# servoUSBrev0.net
KiCad netlist of a schematic drawn in Altium Designer
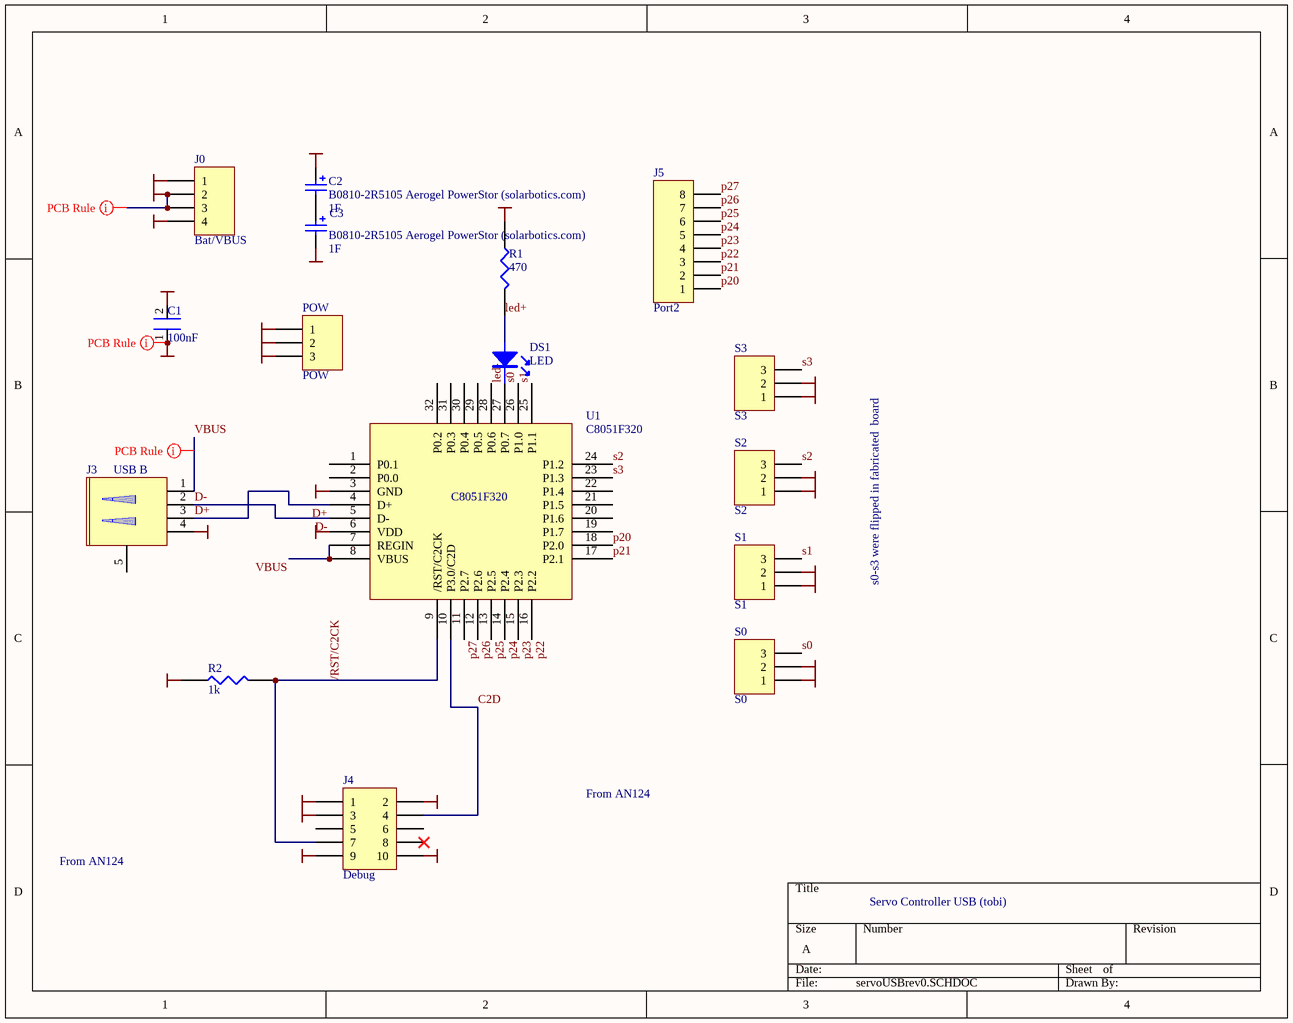
[diagram p0: servoUSBrev0.SCHDOC]

(export (version "E")
  (design (tool "Eeschema 10.0.6"))
  (components
    (comp (ref "C1")
      (value "100nF")
      (footprint "CC2013-0805")
      (libsource (lib "tobi SCHEMATIC") (part "CAPCHIP"))
    )
    (comp (ref "C2")
      (value "B0810-2R5105 Aerogel PowerStor (solarbotics.com)")
      (footprint "Capacitor - Electrolytic:CAPPR3.5-8X10.5")
      (description "Polarized Capacitor (Radial)")
      (fields (field (name "ALTIUM_VALUE") "1F") (field (name "PUBLISHER") "Altium Limited"))
      (libsource (lib "Miscellaneous Devices") (part "Cap Pol1"))
    )
    (comp (ref "C3")
      (value "B0810-2R5105 Aerogel PowerStor (solarbotics.com)")
      (footprint "Capacitor - Electrolytic:CAPPR3.5-8X10.5")
      (description "Polarized Capacitor (Radial)")
      (fields (field (name "ALTIUM_VALUE") "1F") (field (name "PUBLISHER") "Altium Limited"))
      (libsource (lib "Miscellaneous Devices") (part "Cap Pol1"))
    )
    (comp (ref "DS1")
      (value "LED")
      (footprint "0805LED")
      (description "LED, SMT 3mm by 1.5mm")
      (libsource (lib "SimpleMonitorUSBAER") (part "LED"))
    )
    (comp (ref "J0")
      (value "Bat/VBUS")
      (footprint "HDR1X4")
      (description "Header, 4-Pin")
      (fields (field (name "PUBLISHER") "Altium Limited"))
      (libsource (lib "Miscellaneous Connectors") (part "Header 4"))
    )
    (comp (ref "J3")
      (value "USB B")
      (footprint "usb")
      (description "USB TypB")
      (libsource (lib "DAC") (part "USB"))
    )
    (comp (ref "J4")
      (value "Debug")
      (footprint "HDR2X5")
      (description "Header, 5-Pin, Dual row")
      (fields (field (name "PUBLISHER") "Altium Limited"))
      (libsource (lib "Miscellaneous Connectors") (part "Header 5X2"))
    )
    (comp (ref "J5")
      (value "Port2")
      (footprint "HDR1X8")
      (description "Header, 8-Pin")
      (fields (field (name "PUBLISHER") "Altium Limited"))
      (libsource (lib "Miscellaneous Connectors") (part "Header 8"))
    )
    (comp (ref "POW")
      (value "POW")
      (footprint "HDR1X3")
      (description "Header, 3-Pin")
      (fields (field (name "PUBLISHER") "Altium Limited"))
      (libsource (lib "") (part "Header 3_1"))
    )
    (comp (ref "R1") (value "470") (footprint "CR2012-0805") (libsource (lib "*") (part "RES1")))
    (comp (ref "R2") (value "1k") (footprint "CR2012-0805") (libsource (lib "*") (part "RES1")))
    (comp (ref "S0")
      (value "S0")
      (footprint "HDR1X3")
      (description "Header, 3-Pin")
      (fields (field (name "PUBLISHER") "Altium Limited"))
      (libsource (lib "Miscellaneous Connectors") (part "Header 3"))
    )
    (comp (ref "S1")
      (value "S1")
      (footprint "HDR1X3")
      (description "Header, 3-Pin")
      (fields (field (name "PUBLISHER") "Altium Limited"))
      (libsource (lib "Miscellaneous Connectors") (part "Header 3"))
    )
    (comp (ref "S2")
      (value "S2")
      (footprint "HDR1X3")
      (description "Header, 3-Pin")
      (fields (field (name "PUBLISHER") "Altium Limited"))
      (libsource (lib "Miscellaneous Connectors") (part "Header 3"))
    )
    (comp (ref "S3")
      (value "S3")
      (footprint "HDR1X3")
      (description "Header, 3-Pin")
      (fields (field (name "PUBLISHER") "Altium Limited"))
      (libsource (lib "Miscellaneous Connectors") (part "Header 3"))
    )
    (comp (ref "U1")
      (value "C8051F320")
      (footprint "TQFP32")
      (description "Silicon Labs USB Microcontroller")
      (libsource (lib "tobi SCHEMATIC") (part "C8051F320"))
    )
  )
  (nets
    (net (code "1") (name "/C2D") (class "Default")
      (node (ref "J4") (pin "4") (pinfunction "4_4") (pintype "passive"))
      (node (ref "U1") (pin "10") (pinfunction "P3.0/C2D_10") (pintype "passive"))
    )
    (net (code "2") (name "/D+") (class "Default")
      (node (ref "J3") (pin "3") (pintype "passive"))
      (node (ref "U1") (pin "4") (pinfunction "D+_4") (pintype "passive"))
    )
    (net (code "3") (name "/D-") (class "Default")
      (node (ref "J3") (pin "2") (pintype "passive"))
      (node (ref "U1") (pin "5") (pinfunction "D-_5") (pintype "passive"))
    )
    (net (code "4") (name "/led+") (class "Default")
      (node (ref "DS1") (pin "+") (pinfunction "1_+") (pintype "passive"))
      (node (ref "R1") (pin "2") (pinfunction "2_2") (pintype "passive"))
    )
    (net (code "5") (name "/led-") (class "Default")
      (node (ref "DS1") (pin "-") (pinfunction "2_-") (pintype "passive"))
      (node (ref "U1") (pin "27") (pinfunction "P0.7_27") (pintype "passive"))
    )
    (net (code "6") (name "/p20") (class "Default")
      (node (ref "J5") (pin "1") (pinfunction "1_1") (pintype "passive"))
      (node (ref "U1") (pin "18") (pinfunction "P2.0_18") (pintype "passive"))
    )
    (net (code "7") (name "/p21") (class "Default")
      (node (ref "J5") (pin "2") (pinfunction "2_2") (pintype "passive"))
      (node (ref "U1") (pin "17") (pinfunction "P2.1_17") (pintype "passive"))
    )
    (net (code "8") (name "/p22") (class "Default")
      (node (ref "J5") (pin "3") (pinfunction "3_3") (pintype "passive"))
      (node (ref "U1") (pin "16") (pinfunction "P2.2_16") (pintype "passive"))
    )
    (net (code "9") (name "/p23") (class "Default")
      (node (ref "J5") (pin "4") (pinfunction "4_4") (pintype "passive"))
      (node (ref "U1") (pin "15") (pinfunction "P2.3_15") (pintype "passive"))
    )
    (net (code "10") (name "/p24") (class "Default")
      (node (ref "J5") (pin "5") (pinfunction "5_5") (pintype "passive"))
      (node (ref "U1") (pin "14") (pinfunction "P2.4_14") (pintype "passive"))
    )
    (net (code "11") (name "/p25") (class "Default")
      (node (ref "J5") (pin "6") (pinfunction "6_6") (pintype "passive"))
      (node (ref "U1") (pin "13") (pinfunction "P2.5_13") (pintype "passive"))
    )
    (net (code "12") (name "/p26") (class "Default")
      (node (ref "J5") (pin "7") (pinfunction "7_7") (pintype "passive"))
      (node (ref "U1") (pin "12") (pinfunction "P2.6_12") (pintype "passive"))
    )
    (net (code "13") (name "/p27") (class "Default")
      (node (ref "J5") (pin "8") (pinfunction "8_8") (pintype "passive"))
      (node (ref "U1") (pin "11") (pinfunction "P2.7_11") (pintype "passive"))
    )
    (net (code "14") (name "/s0") (class "Default")
      (node (ref "S0") (pin "3") (pinfunction "3_3") (pintype "passive"))
      (node (ref "U1") (pin "26") (pinfunction "P1.0_26") (pintype "passive"))
    )
    (net (code "15") (name "/s1") (class "Default")
      (node (ref "S1") (pin "3") (pinfunction "3_3") (pintype "passive"))
      (node (ref "U1") (pin "25") (pinfunction "P1.1_25") (pintype "passive"))
    )
    (net (code "16") (name "/s2") (class "Default")
      (node (ref "S2") (pin "3") (pinfunction "3_3") (pintype "passive"))
      (node (ref "U1") (pin "24") (pinfunction "P1.2_24") (pintype "passive"))
    )
    (net (code "17") (name "/s3") (class "Default")
      (node (ref "S3") (pin "3") (pinfunction "3_3") (pintype "passive"))
      (node (ref "U1") (pin "23") (pinfunction "P1.3_23") (pintype "passive"))
    )
    (net (code "18") (name "/{slash}RST{slash}C2CK") (class "Default")
      (node (ref "J4") (pin "7") (pinfunction "7_7") (pintype "passive"))
      (node (ref "R2") (pin "2") (pinfunction "2_2") (pintype "passive"))
      (node (ref "U1") (pin "9") (pinfunction "/RST/C2CK_9") (pintype "passive"))
    )
    (net (code "19") (name "GND") (class "Default")
      (node (ref "C1") (pin "1") (pintype "passive"))
      (node (ref "C3") (pin "2") (pinfunction "2_2") (pintype "passive"))
      (node (ref "J0") (pin "1") (pinfunction "1_1") (pintype "passive"))
      (node (ref "J3") (pin "4") (pintype "passive"))
      (node (ref "J4") (pin "2") (pinfunction "2_2") (pintype "passive"))
      (node (ref "J4") (pin "3") (pinfunction "3_3") (pintype "passive"))
      (node (ref "J4") (pin "9") (pinfunction "9_9") (pintype "passive"))
      (node (ref "POW") (pin "1") (pinfunction "1_1") (pintype "passive"))
      (node (ref "S0") (pin "1") (pinfunction "1_1") (pintype "passive"))
      (node (ref "S1") (pin "1") (pinfunction "1_1") (pintype "passive"))
      (node (ref "S2") (pin "1") (pinfunction "1_1") (pintype "passive"))
      (node (ref "S3") (pin "1") (pinfunction "1_1") (pintype "passive"))
      (node (ref "U1") (pin "3") (pinfunction "GND_3") (pintype "passive"))
    )
    (net (code "20") (name "Net-(C2-Pad2)") (class "Default")
      (node (ref "C2") (pin "2") (pinfunction "2_2") (pintype "passive"))
      (node (ref "C3") (pin "1") (pinfunction "1_1") (pintype "passive"))
    )
    (net (code "21") (name "SPOW") (class "Default")
      (node (ref "J0") (pin "2") (pinfunction "2_2") (pintype "passive"))
      (node (ref "J0") (pin "3") (pinfunction "3_3") (pintype "passive"))
      (node (ref "S0") (pin "2") (pinfunction "2_2") (pintype "passive"))
      (node (ref "S1") (pin "2") (pinfunction "2_2") (pintype "passive"))
      (node (ref "S2") (pin "2") (pinfunction "2_2") (pintype "passive"))
      (node (ref "S3") (pin "2") (pinfunction "2_2") (pintype "passive"))
    )
    (net (code "22") (name "VBUS") (class "Default")
      (node (ref "C2") (pin "1") (pinfunction "1_1") (pintype "passive"))
      (node (ref "J0") (pin "4") (pinfunction "4_4") (pintype "passive"))
      (node (ref "J3") (pin "1") (pintype "passive"))
      (node (ref "J4") (pin "10") (pinfunction "10_10") (pintype "passive"))
      (node (ref "POW") (pin "3") (pinfunction "3_3") (pintype "passive"))
      (node (ref "U1") (pin "7") (pinfunction "REGIN_7") (pintype "passive"))
      (node (ref "U1") (pin "8") (pinfunction "VBUS_8") (pintype "passive"))
    )
    (net (code "23") (name "VDD") (class "Default")
      (node (ref "C1") (pin "2") (pintype "passive"))
      (node (ref "J4") (pin "1") (pinfunction "1_1") (pintype "passive"))
      (node (ref "POW") (pin "2") (pinfunction "2_2") (pintype "passive"))
      (node (ref "R1") (pin "1") (pinfunction "1_1") (pintype "passive"))
      (node (ref "R2") (pin "1") (pinfunction "1_1") (pintype "passive"))
      (node (ref "U1") (pin "6") (pinfunction "VDD_6") (pintype "passive"))
    )
    (net (code "24") (name "unconnected-(J3-Pad5)") (class "Default")
      (node (ref "J3") (pin "5") (pintype "passive"))
    )
    (net (code "25") (name "unconnected-(J4-Pad5)") (class "Default")
      (node (ref "J4") (pin "5") (pinfunction "5_5") (pintype "passive"))
    )
    (net (code "26") (name "unconnected-(J4-Pad6)") (class "Default")
      (node (ref "J4") (pin "6") (pinfunction "6_6") (pintype "passive"))
    )
    (net (code "27") (name "unconnected-(J4-Pad8)") (class "Default")
      (node (ref "J4") (pin "8") (pinfunction "8_8") (pintype "passive+no_connect"))
    )
    (net (code "28") (name "unconnected-(U1-P0.0-Pad2)") (class "Default")
      (node (ref "U1") (pin "2") (pinfunction "P0.0_2") (pintype "passive"))
    )
    (net (code "29") (name "unconnected-(U1-P0.1-Pad1)") (class "Default")
      (node (ref "U1") (pin "1") (pinfunction "P0.1_1") (pintype "passive"))
    )
    (net (code "30") (name "unconnected-(U1-P0.2-Pad32)") (class "Default")
      (node (ref "U1") (pin "32") (pinfunction "P0.2_32") (pintype "passive"))
    )
    (net (code "31") (name "unconnected-(U1-P0.3-Pad31)") (class "Default")
      (node (ref "U1") (pin "31") (pinfunction "P0.3_31") (pintype "passive"))
    )
    (net (code "32") (name "unconnected-(U1-P0.4-Pad30)") (class "Default")
      (node (ref "U1") (pin "30") (pinfunction "P0.4_30") (pintype "passive"))
    )
    (net (code "33") (name "unconnected-(U1-P0.5-Pad29)") (class "Default")
      (node (ref "U1") (pin "29") (pinfunction "P0.5_29") (pintype "passive"))
    )
    (net (code "34") (name "unconnected-(U1-P0.6-Pad28)") (class "Default")
      (node (ref "U1") (pin "28") (pinfunction "P0.6_28") (pintype "passive"))
    )
    (net (code "35") (name "unconnected-(U1-P1.4-Pad22)") (class "Default")
      (node (ref "U1") (pin "22") (pinfunction "P1.4_22") (pintype "passive"))
    )
    (net (code "36") (name "unconnected-(U1-P1.5-Pad21)") (class "Default")
      (node (ref "U1") (pin "21") (pinfunction "P1.5_21") (pintype "passive"))
    )
    (net (code "37") (name "unconnected-(U1-P1.6-Pad20)") (class "Default")
      (node (ref "U1") (pin "20") (pinfunction "P1.6_20") (pintype "passive"))
    )
    (net (code "38") (name "unconnected-(U1-P1.7-Pad19)") (class "Default")
      (node (ref "U1") (pin "19") (pinfunction "P1.7_19") (pintype "passive"))
    )
  )
)
